# 4U-4452.net
KiCad netlist of a schematic drawn in EAGLE
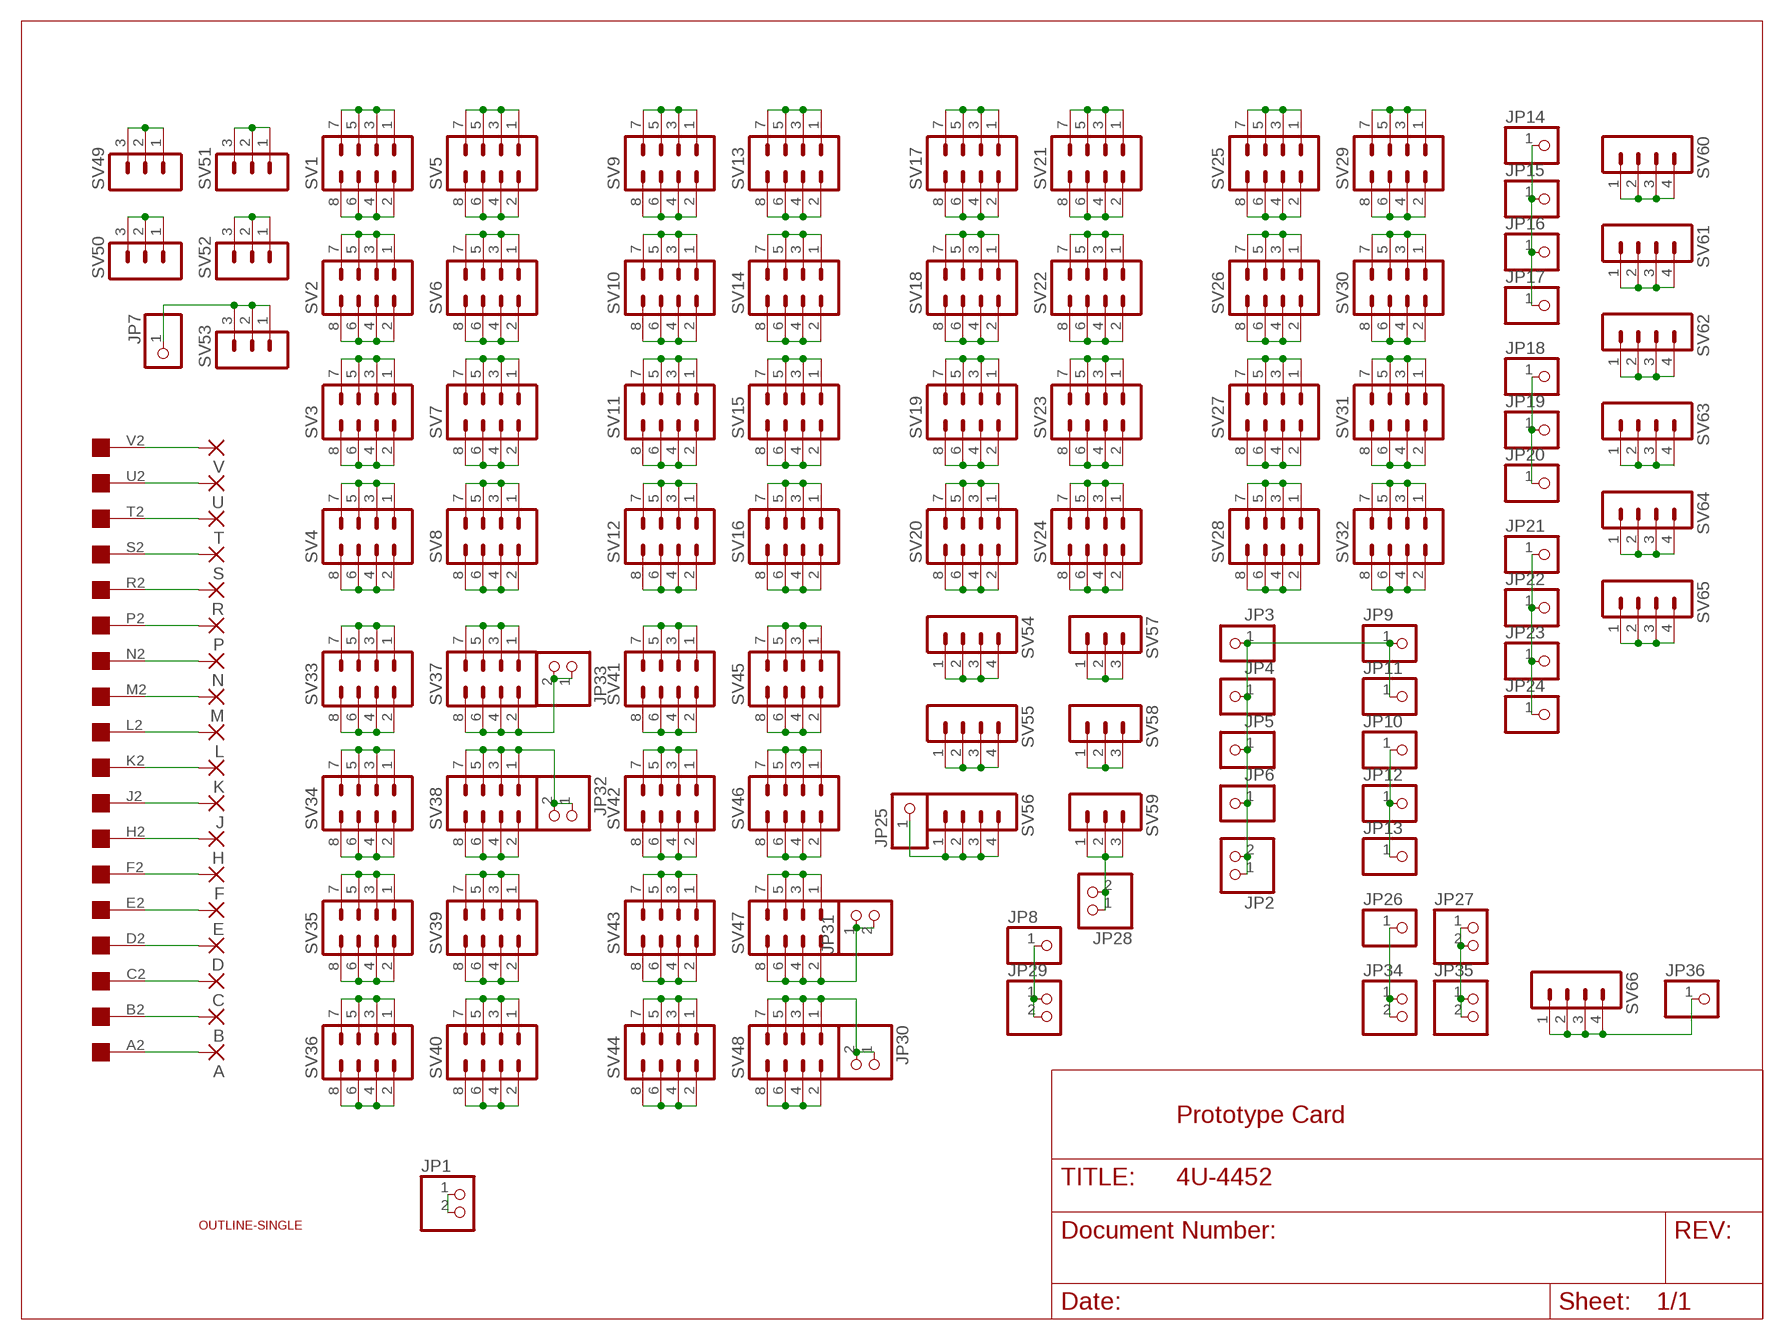
[diagram p0: schematic, sheet 1]

(export (version "E")
  (design (tool "Eeschema 10.0.6"))
  (components
    (comp (ref "A")
      (value "3,17/1,1")
      (footprint "eagle-import:3,17_1,1")
      (libsource (lib "eagle-import") (part "3,17/1,1"))
    )
    (comp (ref "B")
      (value "3,17/1,1")
      (footprint "eagle-import:3,17_1,1")
      (libsource (lib "eagle-import") (part "3,17/1,1"))
    )
    (comp (ref "C")
      (value "3,17/1,1")
      (footprint "eagle-import:3,17_1,1")
      (libsource (lib "eagle-import") (part "3,17/1,1"))
    )
    (comp (ref "D")
      (value "3,17/1,1")
      (footprint "eagle-import:3,17_1,1")
      (libsource (lib "eagle-import") (part "3,17/1,1"))
    )
    (comp (ref "E")
      (value "3,17/1,1")
      (footprint "eagle-import:3,17_1,1")
      (libsource (lib "eagle-import") (part "3,17/1,1"))
    )
    (comp (ref "F")
      (value "3,17/1,1")
      (footprint "eagle-import:3,17_1,1")
      (libsource (lib "eagle-import") (part "3,17/1,1"))
    )
    (comp (ref "H")
      (value "3,17/1,1")
      (footprint "eagle-import:3,17_1,1")
      (libsource (lib "eagle-import") (part "3,17/1,1"))
    )
    (comp (ref "J")
      (value "3,17/1,1")
      (footprint "eagle-import:3,17_1,1")
      (libsource (lib "eagle-import") (part "3,17/1,1"))
    )
    (comp (ref "JP1")
      (value "PINHD-1X2")
      (footprint "eagle-import:1X02")
      (libsource (lib "eagle-import") (part "PINHD-1X2"))
    )
    (comp (ref "JP2")
      (value "PINHD-1X2")
      (footprint "eagle-import:1X02")
      (libsource (lib "eagle-import") (part "PINHD-1X2"))
    )
    (comp (ref "JP3")
      (value "PINHD-1X1")
      (footprint "eagle-import:1X01")
      (libsource (lib "eagle-import") (part "PINHD-1X1"))
    )
    (comp (ref "JP4")
      (value "PINHD-1X1")
      (footprint "eagle-import:1X01")
      (libsource (lib "eagle-import") (part "PINHD-1X1"))
    )
    (comp (ref "JP5")
      (value "PINHD-1X1")
      (footprint "eagle-import:1X01")
      (libsource (lib "eagle-import") (part "PINHD-1X1"))
    )
    (comp (ref "JP6")
      (value "PINHD-1X1")
      (footprint "eagle-import:1X01")
      (libsource (lib "eagle-import") (part "PINHD-1X1"))
    )
    (comp (ref "JP7")
      (value "PINHD-1X1")
      (footprint "eagle-import:1X01")
      (libsource (lib "eagle-import") (part "PINHD-1X1"))
    )
    (comp (ref "JP8")
      (value "PINHD-1X1")
      (footprint "eagle-import:1X01")
      (libsource (lib "eagle-import") (part "PINHD-1X1"))
    )
    (comp (ref "JP9")
      (value "PINHD-1X1")
      (footprint "eagle-import:1X01")
      (libsource (lib "eagle-import") (part "PINHD-1X1"))
    )
    (comp (ref "JP10")
      (value "PINHD-1X1")
      (footprint "eagle-import:1X01")
      (libsource (lib "eagle-import") (part "PINHD-1X1"))
    )
    (comp (ref "JP11")
      (value "PINHD-1X1")
      (footprint "eagle-import:1X01")
      (libsource (lib "eagle-import") (part "PINHD-1X1"))
    )
    (comp (ref "JP12")
      (value "PINHD-1X1")
      (footprint "eagle-import:1X01")
      (libsource (lib "eagle-import") (part "PINHD-1X1"))
    )
    (comp (ref "JP13")
      (value "PINHD-1X1")
      (footprint "eagle-import:1X01")
      (libsource (lib "eagle-import") (part "PINHD-1X1"))
    )
    (comp (ref "JP14")
      (value "PINHD-1X1")
      (footprint "eagle-import:1X01")
      (libsource (lib "eagle-import") (part "PINHD-1X1"))
    )
    (comp (ref "JP15")
      (value "PINHD-1X1")
      (footprint "eagle-import:1X01")
      (libsource (lib "eagle-import") (part "PINHD-1X1"))
    )
    (comp (ref "JP16")
      (value "PINHD-1X1")
      (footprint "eagle-import:1X01")
      (libsource (lib "eagle-import") (part "PINHD-1X1"))
    )
    (comp (ref "JP17")
      (value "PINHD-1X1")
      (footprint "eagle-import:1X01")
      (libsource (lib "eagle-import") (part "PINHD-1X1"))
    )
    (comp (ref "JP18")
      (value "PINHD-1X1")
      (footprint "eagle-import:1X01")
      (libsource (lib "eagle-import") (part "PINHD-1X1"))
    )
    (comp (ref "JP19")
      (value "PINHD-1X1")
      (footprint "eagle-import:1X01")
      (libsource (lib "eagle-import") (part "PINHD-1X1"))
    )
    (comp (ref "JP20")
      (value "PINHD-1X1")
      (footprint "eagle-import:1X01")
      (libsource (lib "eagle-import") (part "PINHD-1X1"))
    )
    (comp (ref "JP21")
      (value "PINHD-1X1")
      (footprint "eagle-import:1X01")
      (libsource (lib "eagle-import") (part "PINHD-1X1"))
    )
    (comp (ref "JP22")
      (value "PINHD-1X1")
      (footprint "eagle-import:1X01")
      (libsource (lib "eagle-import") (part "PINHD-1X1"))
    )
    (comp (ref "JP23")
      (value "PINHD-1X1")
      (footprint "eagle-import:1X01")
      (libsource (lib "eagle-import") (part "PINHD-1X1"))
    )
    (comp (ref "JP24")
      (value "PINHD-1X1")
      (footprint "eagle-import:1X01")
      (libsource (lib "eagle-import") (part "PINHD-1X1"))
    )
    (comp (ref "JP25")
      (value "PINHD-1X1")
      (footprint "eagle-import:1X01")
      (libsource (lib "eagle-import") (part "PINHD-1X1"))
    )
    (comp (ref "JP26")
      (value "PINHD-1X1")
      (footprint "eagle-import:1X01")
      (libsource (lib "eagle-import") (part "PINHD-1X1"))
    )
    (comp (ref "JP27")
      (value "PINHD-1X2")
      (footprint "eagle-import:1X02")
      (libsource (lib "eagle-import") (part "PINHD-1X2"))
    )
    (comp (ref "JP28")
      (value "PINHD-1X2")
      (footprint "eagle-import:1X02")
      (libsource (lib "eagle-import") (part "PINHD-1X2"))
    )
    (comp (ref "JP29")
      (value "PINHD-1X2")
      (footprint "eagle-import:1X02")
      (libsource (lib "eagle-import") (part "PINHD-1X2"))
    )
    (comp (ref "JP30")
      (value "PINHD-1X2")
      (footprint "eagle-import:1X02")
      (libsource (lib "eagle-import") (part "PINHD-1X2"))
    )
    (comp (ref "JP31")
      (value "PINHD-1X2")
      (footprint "eagle-import:1X02")
      (libsource (lib "eagle-import") (part "PINHD-1X2"))
    )
    (comp (ref "JP32")
      (value "PINHD-1X2")
      (footprint "eagle-import:1X02")
      (libsource (lib "eagle-import") (part "PINHD-1X2"))
    )
    (comp (ref "JP33")
      (value "PINHD-1X2")
      (footprint "eagle-import:1X02")
      (libsource (lib "eagle-import") (part "PINHD-1X2"))
    )
    (comp (ref "JP34")
      (value "PINHD-1X2")
      (footprint "eagle-import:1X02")
      (libsource (lib "eagle-import") (part "PINHD-1X2"))
    )
    (comp (ref "JP35")
      (value "PINHD-1X2")
      (footprint "eagle-import:1X02")
      (libsource (lib "eagle-import") (part "PINHD-1X2"))
    )
    (comp (ref "JP36")
      (value "PINHD-1X1")
      (footprint "eagle-import:1X01")
      (libsource (lib "eagle-import") (part "PINHD-1X1"))
    )
    (comp (ref "K")
      (value "3,17/1,1")
      (footprint "eagle-import:3,17_1,1")
      (libsource (lib "eagle-import") (part "3,17/1,1"))
    )
    (comp (ref "L")
      (value "3,17/1,1")
      (footprint "eagle-import:3,17_1,1")
      (libsource (lib "eagle-import") (part "3,17/1,1"))
    )
    (comp (ref "M")
      (value "3,17/1,1")
      (footprint "eagle-import:3,17_1,1")
      (libsource (lib "eagle-import") (part "3,17/1,1"))
    )
    (comp (ref "N")
      (value "3,17/1,1")
      (footprint "eagle-import:3,17_1,1")
      (libsource (lib "eagle-import") (part "3,17/1,1"))
    )
    (comp (ref "P")
      (value "3,17/1,1")
      (footprint "eagle-import:3,17_1,1")
      (libsource (lib "eagle-import") (part "3,17/1,1"))
    )
    (comp (ref "R")
      (value "3,17/1,1")
      (footprint "eagle-import:3,17_1,1")
      (libsource (lib "eagle-import") (part "3,17/1,1"))
    )
    (comp (ref "S")
      (value "3,17/1,1")
      (footprint "eagle-import:3,17_1,1")
      (libsource (lib "eagle-import") (part "3,17/1,1"))
    )
    (comp (ref "SV1")
      (value "MA04-2")
      (footprint "eagle-import:MA04-2")
      (libsource (lib "eagle-import") (part "MA04-2"))
    )
    (comp (ref "SV2")
      (value "MA04-2")
      (footprint "eagle-import:MA04-2")
      (libsource (lib "eagle-import") (part "MA04-2"))
    )
    (comp (ref "SV3")
      (value "MA04-2")
      (footprint "eagle-import:MA04-2")
      (libsource (lib "eagle-import") (part "MA04-2"))
    )
    (comp (ref "SV4")
      (value "MA04-2")
      (footprint "eagle-import:MA04-2")
      (libsource (lib "eagle-import") (part "MA04-2"))
    )
    (comp (ref "SV5")
      (value "MA04-2")
      (footprint "eagle-import:MA04-2")
      (libsource (lib "eagle-import") (part "MA04-2"))
    )
    (comp (ref "SV6")
      (value "MA04-2")
      (footprint "eagle-import:MA04-2")
      (libsource (lib "eagle-import") (part "MA04-2"))
    )
    (comp (ref "SV7")
      (value "MA04-2")
      (footprint "eagle-import:MA04-2")
      (libsource (lib "eagle-import") (part "MA04-2"))
    )
    (comp (ref "SV8")
      (value "MA04-2")
      (footprint "eagle-import:MA04-2")
      (libsource (lib "eagle-import") (part "MA04-2"))
    )
    (comp (ref "SV9")
      (value "MA04-2")
      (footprint "eagle-import:MA04-2")
      (libsource (lib "eagle-import") (part "MA04-2"))
    )
    (comp (ref "SV10")
      (value "MA04-2")
      (footprint "eagle-import:MA04-2")
      (libsource (lib "eagle-import") (part "MA04-2"))
    )
    (comp (ref "SV11")
      (value "MA04-2")
      (footprint "eagle-import:MA04-2")
      (libsource (lib "eagle-import") (part "MA04-2"))
    )
    (comp (ref "SV12")
      (value "MA04-2")
      (footprint "eagle-import:MA04-2")
      (libsource (lib "eagle-import") (part "MA04-2"))
    )
    (comp (ref "SV13")
      (value "MA04-2")
      (footprint "eagle-import:MA04-2")
      (libsource (lib "eagle-import") (part "MA04-2"))
    )
    (comp (ref "SV14")
      (value "MA04-2")
      (footprint "eagle-import:MA04-2")
      (libsource (lib "eagle-import") (part "MA04-2"))
    )
    (comp (ref "SV15")
      (value "MA04-2")
      (footprint "eagle-import:MA04-2")
      (libsource (lib "eagle-import") (part "MA04-2"))
    )
    (comp (ref "SV16")
      (value "MA04-2")
      (footprint "eagle-import:MA04-2")
      (libsource (lib "eagle-import") (part "MA04-2"))
    )
    (comp (ref "SV17")
      (value "MA04-2")
      (footprint "eagle-import:MA04-2")
      (libsource (lib "eagle-import") (part "MA04-2"))
    )
    (comp (ref "SV18")
      (value "MA04-2")
      (footprint "eagle-import:MA04-2")
      (libsource (lib "eagle-import") (part "MA04-2"))
    )
    (comp (ref "SV19")
      (value "MA04-2")
      (footprint "eagle-import:MA04-2")
      (libsource (lib "eagle-import") (part "MA04-2"))
    )
    (comp (ref "SV20")
      (value "MA04-2")
      (footprint "eagle-import:MA04-2")
      (libsource (lib "eagle-import") (part "MA04-2"))
    )
    (comp (ref "SV21")
      (value "MA04-2")
      (footprint "eagle-import:MA04-2")
      (libsource (lib "eagle-import") (part "MA04-2"))
    )
    (comp (ref "SV22")
      (value "MA04-2")
      (footprint "eagle-import:MA04-2")
      (libsource (lib "eagle-import") (part "MA04-2"))
    )
    (comp (ref "SV23")
      (value "MA04-2")
      (footprint "eagle-import:MA04-2")
      (libsource (lib "eagle-import") (part "MA04-2"))
    )
    (comp (ref "SV24")
      (value "MA04-2")
      (footprint "eagle-import:MA04-2")
      (libsource (lib "eagle-import") (part "MA04-2"))
    )
    (comp (ref "SV25")
      (value "MA04-2")
      (footprint "eagle-import:MA04-2")
      (libsource (lib "eagle-import") (part "MA04-2"))
    )
    (comp (ref "SV26")
      (value "MA04-2")
      (footprint "eagle-import:MA04-2")
      (libsource (lib "eagle-import") (part "MA04-2"))
    )
    (comp (ref "SV27")
      (value "MA04-2")
      (footprint "eagle-import:MA04-2")
      (libsource (lib "eagle-import") (part "MA04-2"))
    )
    (comp (ref "SV28")
      (value "MA04-2")
      (footprint "eagle-import:MA04-2")
      (libsource (lib "eagle-import") (part "MA04-2"))
    )
    (comp (ref "SV29")
      (value "MA04-2")
      (footprint "eagle-import:MA04-2")
      (libsource (lib "eagle-import") (part "MA04-2"))
    )
    (comp (ref "SV30")
      (value "MA04-2")
      (footprint "eagle-import:MA04-2")
      (libsource (lib "eagle-import") (part "MA04-2"))
    )
    (comp (ref "SV31")
      (value "MA04-2")
      (footprint "eagle-import:MA04-2")
      (libsource (lib "eagle-import") (part "MA04-2"))
    )
    (comp (ref "SV32")
      (value "MA04-2")
      (footprint "eagle-import:MA04-2")
      (libsource (lib "eagle-import") (part "MA04-2"))
    )
    (comp (ref "SV33")
      (value "MA04-2")
      (footprint "eagle-import:MA04-2")
      (libsource (lib "eagle-import") (part "MA04-2"))
    )
    (comp (ref "SV34")
      (value "MA04-2")
      (footprint "eagle-import:MA04-2")
      (libsource (lib "eagle-import") (part "MA04-2"))
    )
    (comp (ref "SV35")
      (value "MA04-2")
      (footprint "eagle-import:MA04-2")
      (libsource (lib "eagle-import") (part "MA04-2"))
    )
    (comp (ref "SV36")
      (value "MA04-2")
      (footprint "eagle-import:MA04-2")
      (libsource (lib "eagle-import") (part "MA04-2"))
    )
    (comp (ref "SV37")
      (value "MA04-2")
      (footprint "eagle-import:MA04-2")
      (libsource (lib "eagle-import") (part "MA04-2"))
    )
    (comp (ref "SV38")
      (value "MA04-2")
      (footprint "eagle-import:MA04-2")
      (libsource (lib "eagle-import") (part "MA04-2"))
    )
    (comp (ref "SV39")
      (value "MA04-2")
      (footprint "eagle-import:MA04-2")
      (libsource (lib "eagle-import") (part "MA04-2"))
    )
    (comp (ref "SV40")
      (value "MA04-2")
      (footprint "eagle-import:MA04-2")
      (libsource (lib "eagle-import") (part "MA04-2"))
    )
    (comp (ref "SV41")
      (value "MA04-2")
      (footprint "eagle-import:MA04-2")
      (libsource (lib "eagle-import") (part "MA04-2"))
    )
    (comp (ref "SV42")
      (value "MA04-2")
      (footprint "eagle-import:MA04-2")
      (libsource (lib "eagle-import") (part "MA04-2"))
    )
    (comp (ref "SV43")
      (value "MA04-2")
      (footprint "eagle-import:MA04-2")
      (libsource (lib "eagle-import") (part "MA04-2"))
    )
    (comp (ref "SV44")
      (value "MA04-2")
      (footprint "eagle-import:MA04-2")
      (libsource (lib "eagle-import") (part "MA04-2"))
    )
    (comp (ref "SV45")
      (value "MA04-2")
      (footprint "eagle-import:MA04-2")
      (libsource (lib "eagle-import") (part "MA04-2"))
    )
    (comp (ref "SV46")
      (value "MA04-2")
      (footprint "eagle-import:MA04-2")
      (libsource (lib "eagle-import") (part "MA04-2"))
    )
    (comp (ref "SV47")
      (value "MA04-2")
      (footprint "eagle-import:MA04-2")
      (libsource (lib "eagle-import") (part "MA04-2"))
    )
    (comp (ref "SV48")
      (value "MA04-2")
      (footprint "eagle-import:MA04-2")
      (libsource (lib "eagle-import") (part "MA04-2"))
    )
    (comp (ref "SV49")
      (value "MA03-1")
      (footprint "eagle-import:MA03-1")
      (libsource (lib "eagle-import") (part "MA03-1"))
    )
    (comp (ref "SV50")
      (value "MA03-1")
      (footprint "eagle-import:MA03-1")
      (libsource (lib "eagle-import") (part "MA03-1"))
    )
    (comp (ref "SV51")
      (value "MA03-1")
      (footprint "eagle-import:MA03-1")
      (libsource (lib "eagle-import") (part "MA03-1"))
    )
    (comp (ref "SV52")
      (value "MA03-1")
      (footprint "eagle-import:MA03-1")
      (libsource (lib "eagle-import") (part "MA03-1"))
    )
    (comp (ref "SV53")
      (value "MA03-1")
      (footprint "eagle-import:MA03-1")
      (libsource (lib "eagle-import") (part "MA03-1"))
    )
    (comp (ref "SV54")
      (value "MA04-1")
      (footprint "eagle-import:MA04-1")
      (libsource (lib "eagle-import") (part "MA04-1"))
    )
    (comp (ref "SV55")
      (value "MA04-1")
      (footprint "eagle-import:MA04-1")
      (libsource (lib "eagle-import") (part "MA04-1"))
    )
    (comp (ref "SV56")
      (value "MA04-1")
      (footprint "eagle-import:MA04-1")
      (libsource (lib "eagle-import") (part "MA04-1"))
    )
    (comp (ref "SV57")
      (value "MA03-1")
      (footprint "eagle-import:MA03-1")
      (libsource (lib "eagle-import") (part "MA03-1"))
    )
    (comp (ref "SV58")
      (value "MA03-1")
      (footprint "eagle-import:MA03-1")
      (libsource (lib "eagle-import") (part "MA03-1"))
    )
    (comp (ref "SV59")
      (value "MA03-1")
      (footprint "eagle-import:MA03-1")
      (libsource (lib "eagle-import") (part "MA03-1"))
    )
    (comp (ref "SV60")
      (value "MA04-1")
      (footprint "eagle-import:MA04-1")
      (libsource (lib "eagle-import") (part "MA04-1"))
    )
    (comp (ref "SV61")
      (value "MA04-1")
      (footprint "eagle-import:MA04-1")
      (libsource (lib "eagle-import") (part "MA04-1"))
    )
    (comp (ref "SV62")
      (value "MA04-1")
      (footprint "eagle-import:MA04-1")
      (libsource (lib "eagle-import") (part "MA04-1"))
    )
    (comp (ref "SV63")
      (value "MA04-1")
      (footprint "eagle-import:MA04-1")
      (libsource (lib "eagle-import") (part "MA04-1"))
    )
    (comp (ref "SV64")
      (value "MA04-1")
      (footprint "eagle-import:MA04-1")
      (libsource (lib "eagle-import") (part "MA04-1"))
    )
    (comp (ref "SV65")
      (value "MA04-1")
      (footprint "eagle-import:MA04-1")
      (libsource (lib "eagle-import") (part "MA04-1"))
    )
    (comp (ref "SV66")
      (value "MA04-1")
      (footprint "eagle-import:MA04-1")
      (libsource (lib "eagle-import") (part "MA04-1"))
    )
    (comp (ref "T")
      (value "3,17/1,1")
      (footprint "eagle-import:3,17_1,1")
      (libsource (lib "eagle-import") (part "3,17/1,1"))
    )
    (comp (ref "U")
      (value "3,17/1,1")
      (footprint "eagle-import:3,17_1,1")
      (libsource (lib "eagle-import") (part "3,17/1,1"))
    )
    (comp (ref "U$1")
      (value "EDGE-1")
      (footprint "eagle-import:EDGE-CON1")
      (libsource (lib "eagle-import") (part "EDGE-1"))
    )
    (comp (ref "U$2")
      (value "OUTLINE-SINGLE")
      (footprint "eagle-import:SINGLE")
      (libsource (lib "eagle-import") (part "OUTLINE-SINGLE"))
    )
    (comp (ref "V")
      (value "3,17/1,1")
      (footprint "eagle-import:3,17_1,1")
      (libsource (lib "eagle-import") (part "3,17/1,1"))
    )
  )
  (nets
    (net (code "1") (name "Net-(A-P)") (class "Default")
      (node (ref "A") (pin "1") (pinfunction "P_1") (pintype "passive"))
      (node (ref "U$1") (pin "A2") (pinfunction "1_A2") (pintype "bidirectional"))
    )
    (net (code "2") (name "Net-(B-P)") (class "Default")
      (node (ref "B") (pin "1") (pinfunction "P_1") (pintype "passive"))
      (node (ref "U$1") (pin "B2") (pinfunction "1_B2") (pintype "bidirectional"))
    )
    (net (code "3") (name "Net-(C-P)") (class "Default")
      (node (ref "C") (pin "1") (pinfunction "P_1") (pintype "passive"))
      (node (ref "U$1") (pin "C2") (pinfunction "1_C2") (pintype "bidirectional"))
    )
    (net (code "4") (name "Net-(D-P)") (class "Default")
      (node (ref "D") (pin "1") (pinfunction "P_1") (pintype "passive"))
      (node (ref "U$1") (pin "D2") (pinfunction "1_D2") (pintype "bidirectional"))
    )
    (net (code "5") (name "Net-(E-P)") (class "Default")
      (node (ref "E") (pin "1") (pinfunction "P_1") (pintype "passive"))
      (node (ref "U$1") (pin "E2") (pinfunction "1_E2") (pintype "bidirectional"))
    )
    (net (code "6") (name "Net-(F-P)") (class "Default")
      (node (ref "F") (pin "1") (pinfunction "P_1") (pintype "passive"))
      (node (ref "U$1") (pin "F2") (pinfunction "1_F2") (pintype "bidirectional"))
    )
    (net (code "7") (name "Net-(H-P)") (class "Default")
      (node (ref "H") (pin "1") (pinfunction "P_1") (pintype "passive"))
      (node (ref "U$1") (pin "H2") (pinfunction "1_H2") (pintype "bidirectional"))
    )
    (net (code "8") (name "Net-(J-P)") (class "Default")
      (node (ref "J") (pin "1") (pinfunction "P_1") (pintype "passive"))
      (node (ref "U$1") (pin "J2") (pinfunction "1_J2") (pintype "bidirectional"))
    )
    (net (code "9") (name "Net-(JP1-Pad1)") (class "Default")
      (node (ref "JP1") (pin "1") (pinfunction "1_1") (pintype "passive"))
      (node (ref "JP1") (pin "2") (pinfunction "2_2") (pintype "passive"))
    )
    (net (code "10") (name "Net-(JP7-Pad1)") (class "Default")
      (node (ref "JP7") (pin "1") (pinfunction "1_1") (pintype "passive"))
      (node (ref "SV53") (pin "1") (pinfunction "1_1") (pintype "passive"))
      (node (ref "SV53") (pin "2") (pinfunction "2_2") (pintype "passive"))
      (node (ref "SV53") (pin "3") (pinfunction "3_3") (pintype "passive"))
    )
    (net (code "11") (name "Net-(JP10-Pad1)") (class "Default")
      (node (ref "JP10") (pin "1") (pinfunction "1_1") (pintype "passive"))
      (node (ref "JP12") (pin "1") (pinfunction "1_1") (pintype "passive"))
      (node (ref "JP13") (pin "1") (pinfunction "1_1") (pintype "passive"))
    )
    (net (code "12") (name "Net-(JP11-Pad1)") (class "Default")
      (node (ref "JP11") (pin "1") (pinfunction "1_1") (pintype "passive"))
      (node (ref "JP2") (pin "1") (pinfunction "1_1") (pintype "passive"))
      (node (ref "JP2") (pin "2") (pinfunction "2_2") (pintype "passive"))
      (node (ref "JP3") (pin "1") (pinfunction "1_1") (pintype "passive"))
      (node (ref "JP4") (pin "1") (pinfunction "1_1") (pintype "passive"))
      (node (ref "JP5") (pin "1") (pinfunction "1_1") (pintype "passive"))
      (node (ref "JP6") (pin "1") (pinfunction "1_1") (pintype "passive"))
      (node (ref "JP9") (pin "1") (pinfunction "1_1") (pintype "passive"))
    )
    (net (code "13") (name "Net-(JP14-Pad1)") (class "Default")
      (node (ref "JP14") (pin "1") (pinfunction "1_1") (pintype "passive"))
      (node (ref "JP15") (pin "1") (pinfunction "1_1") (pintype "passive"))
      (node (ref "JP16") (pin "1") (pinfunction "1_1") (pintype "passive"))
      (node (ref "JP17") (pin "1") (pinfunction "1_1") (pintype "passive"))
    )
    (net (code "14") (name "Net-(JP18-Pad1)") (class "Default")
      (node (ref "JP18") (pin "1") (pinfunction "1_1") (pintype "passive"))
      (node (ref "JP19") (pin "1") (pinfunction "1_1") (pintype "passive"))
      (node (ref "JP20") (pin "1") (pinfunction "1_1") (pintype "passive"))
    )
    (net (code "15") (name "Net-(JP21-Pad1)") (class "Default")
      (node (ref "JP21") (pin "1") (pinfunction "1_1") (pintype "passive"))
      (node (ref "JP22") (pin "1") (pinfunction "1_1") (pintype "passive"))
      (node (ref "JP23") (pin "1") (pinfunction "1_1") (pintype "passive"))
      (node (ref "JP24") (pin "1") (pinfunction "1_1") (pintype "passive"))
    )
    (net (code "16") (name "Net-(JP25-Pad1)") (class "Default")
      (node (ref "JP25") (pin "1") (pinfunction "1_1") (pintype "passive"))
      (node (ref "SV56") (pin "1") (pinfunction "1_1") (pintype "passive"))
      (node (ref "SV56") (pin "2") (pinfunction "2_2") (pintype "passive"))
      (node (ref "SV56") (pin "3") (pinfunction "3_3") (pintype "passive"))
      (node (ref "SV56") (pin "4") (pinfunction "4_4") (pintype "passive"))
    )
    (net (code "17") (name "Net-(JP26-Pad1)") (class "Default")
      (node (ref "JP26") (pin "1") (pinfunction "1_1") (pintype "passive"))
      (node (ref "JP34") (pin "1") (pinfunction "1_1") (pintype "passive"))
      (node (ref "JP34") (pin "2") (pinfunction "2_2") (pintype "passive"))
    )
    (net (code "18") (name "Net-(JP27-Pad1)") (class "Default")
      (node (ref "JP27") (pin "1") (pinfunction "1_1") (pintype "passive"))
      (node (ref "JP27") (pin "2") (pinfunction "2_2") (pintype "passive"))
      (node (ref "JP35") (pin "1") (pinfunction "1_1") (pintype "passive"))
      (node (ref "JP35") (pin "2") (pinfunction "2_2") (pintype "passive"))
    )
    (net (code "19") (name "Net-(JP28-Pad1)") (class "Default")
      (node (ref "JP28") (pin "1") (pinfunction "1_1") (pintype "passive"))
      (node (ref "JP28") (pin "2") (pinfunction "2_2") (pintype "passive"))
      (node (ref "SV59") (pin "1") (pinfunction "1_1") (pintype "passive"))
      (node (ref "SV59") (pin "2") (pinfunction "2_2") (pintype "passive"))
      (node (ref "SV59") (pin "3") (pinfunction "3_3") (pintype "passive"))
    )
    (net (code "20") (name "Net-(JP29-Pad1)") (class "Default")
      (node (ref "JP29") (pin "1") (pinfunction "1_1") (pintype "passive"))
      (node (ref "JP29") (pin "2") (pinfunction "2_2") (pintype "passive"))
      (node (ref "JP8") (pin "1") (pinfunction "1_1") (pintype "passive"))
    )
    (net (code "21") (name "Net-(JP30-Pad1)") (class "Default")
      (node (ref "JP30") (pin "1") (pinfunction "1_1") (pintype "passive"))
      (node (ref "JP30") (pin "2") (pinfunction "2_2") (pintype "passive"))
      (node (ref "SV48") (pin "1") (pinfunction "1_1") (pintype "passive"))
      (node (ref "SV48") (pin "3") (pinfunction "3_3") (pintype "passive"))
      (node (ref "SV48") (pin "5") (pinfunction "5_5") (pintype "passive"))
      (node (ref "SV48") (pin "7") (pinfunction "7_7") (pintype "passive"))
    )
    (net (code "22") (name "Net-(JP31-Pad1)") (class "Default")
      (node (ref "JP31") (pin "1") (pinfunction "1_1") (pintype "passive"))
      (node (ref "JP31") (pin "2") (pinfunction "2_2") (pintype "passive"))
      (node (ref "SV47") (pin "2") (pinfunction "2_2") (pintype "passive"))
      (node (ref "SV47") (pin "4") (pinfunction "4_4") (pintype "passive"))
      (node (ref "SV47") (pin "6") (pinfunction "6_6") (pintype "passive"))
      (node (ref "SV47") (pin "8") (pinfunction "8_8") (pintype "passive"))
    )
    (net (code "23") (name "Net-(JP32-Pad1)") (class "Default")
      (node (ref "JP32") (pin "1") (pinfunction "1_1") (pintype "passive"))
      (node (ref "JP32") (pin "2") (pinfunction "2_2") (pintype "passive"))
      (node (ref "SV38") (pin "1") (pinfunction "1_1") (pintype "passive"))
      (node (ref "SV38") (pin "3") (pinfunction "3_3") (pintype "passive"))
      (node (ref "SV38") (pin "5") (pinfunction "5_5") (pintype "passive"))
      (node (ref "SV38") (pin "7") (pinfunction "7_7") (pintype "passive"))
    )
    (net (code "24") (name "Net-(JP33-Pad1)") (class "Default")
      (node (ref "JP33") (pin "1") (pinfunction "1_1") (pintype "passive"))
      (node (ref "JP33") (pin "2") (pinfunction "2_2") (pintype "passive"))
      (node (ref "SV37") (pin "2") (pinfunction "2_2") (pintype "passive"))
      (node (ref "SV37") (pin "4") (pinfunction "4_4") (pintype "passive"))
      (node (ref "SV37") (pin "6") (pinfunction "6_6") (pintype "passive"))
      (node (ref "SV37") (pin "8") (pinfunction "8_8") (pintype "passive"))
    )
    (net (code "25") (name "Net-(JP36-Pad1)") (class "Default")
      (node (ref "JP36") (pin "1") (pinfunction "1_1") (pintype "passive"))
      (node (ref "SV66") (pin "1") (pinfunction "1_1") (pintype "passive"))
      (node (ref "SV66") (pin "2") (pinfunction "2_2") (pintype "passive"))
      (node (ref "SV66") (pin "3") (pinfunction "3_3") (pintype "passive"))
      (node (ref "SV66") (pin "4") (pinfunction "4_4") (pintype "passive"))
    )
    (net (code "26") (name "Net-(K-P)") (class "Default")
      (node (ref "K") (pin "1") (pinfunction "P_1") (pintype "passive"))
      (node (ref "U$1") (pin "K2") (pinfunction "1_K2") (pintype "bidirectional"))
    )
    (net (code "27") (name "Net-(L-P)") (class "Default")
      (node (ref "L") (pin "1") (pinfunction "P_1") (pintype "passive"))
      (node (ref "U$1") (pin "L2") (pinfunction "1_L2") (pintype "bidirectional"))
    )
    (net (code "28") (name "Net-(M-P)") (class "Default")
      (node (ref "M") (pin "1") (pinfunction "P_1") (pintype "passive"))
      (node (ref "U$1") (pin "M2") (pinfunction "1_M2") (pintype "bidirectional"))
    )
    (net (code "29") (name "Net-(N-P)") (class "Default")
      (node (ref "N") (pin "1") (pinfunction "P_1") (pintype "passive"))
      (node (ref "U$1") (pin "N2") (pinfunction "1_N2") (pintype "bidirectional"))
    )
    (net (code "30") (name "Net-(P-P)") (class "Default")
      (node (ref "P") (pin "1") (pinfunction "P_1") (pintype "passive"))
      (node (ref "U$1") (pin "P2") (pinfunction "1_P2") (pintype "bidirectional"))
    )
    (net (code "31") (name "Net-(R-P)") (class "Default")
      (node (ref "R") (pin "1") (pinfunction "P_1") (pintype "passive"))
      (node (ref "U$1") (pin "R2") (pinfunction "1_R2") (pintype "bidirectional"))
    )
    (net (code "32") (name "Net-(S-P)") (class "Default")
      (node (ref "S") (pin "1") (pinfunction "P_1") (pintype "passive"))
      (node (ref "U$1") (pin "S2") (pinfunction "1_S2") (pintype "bidirectional"))
    )
    (net (code "33") (name "Net-(SV1-Pad1)") (class "Default")
      (node (ref "SV1") (pin "1") (pinfunction "1_1") (pintype "passive"))
      (node (ref "SV1") (pin "3") (pinfunction "3_3") (pintype "passive"))
      (node (ref "SV1") (pin "5") (pinfunction "5_5") (pintype "passive"))
      (node (ref "SV1") (pin "7") (pinfunction "7_7") (pintype "passive"))
    )
    (net (code "34") (name "Net-(SV1-Pad2)") (class "Default")
      (node (ref "SV1") (pin "2") (pinfunction "2_2") (pintype "passive"))
      (node (ref "SV1") (pin "4") (pinfunction "4_4") (pintype "passive"))
      (node (ref "SV1") (pin "6") (pinfunction "6_6") (pintype "passive"))
      (node (ref "SV1") (pin "8") (pinfunction "8_8") (pintype "passive"))
    )
    (net (code "35") (name "Net-(SV2-Pad1)") (class "Default")
      (node (ref "SV2") (pin "1") (pinfunction "1_1") (pintype "passive"))
      (node (ref "SV2") (pin "3") (pinfunction "3_3") (pintype "passive"))
      (node (ref "SV2") (pin "5") (pinfunction "5_5") (pintype "passive"))
      (node (ref "SV2") (pin "7") (pinfunction "7_7") (pintype "passive"))
    )
    (net (code "36") (name "Net-(SV2-Pad2)") (class "Default")
      (node (ref "SV2") (pin "2") (pinfunction "2_2") (pintype "passive"))
      (node (ref "SV2") (pin "4") (pinfunction "4_4") (pintype "passive"))
      (node (ref "SV2") (pin "6") (pinfunction "6_6") (pintype "passive"))
      (node (ref "SV2") (pin "8") (pinfunction "8_8") (pintype "passive"))
    )
    (net (code "37") (name "Net-(SV3-Pad1)") (class "Default")
      (node (ref "SV3") (pin "1") (pinfunction "1_1") (pintype "passive"))
      (node (ref "SV3") (pin "3") (pinfunction "3_3") (pintype "passive"))
      (node (ref "SV3") (pin "5") (pinfunction "5_5") (pintype "passive"))
      (node (ref "SV3") (pin "7") (pinfunction "7_7") (pintype "passive"))
    )
    (net (code "38") (name "Net-(SV3-Pad2)") (class "Default")
      (node (ref "SV3") (pin "2") (pinfunction "2_2") (pintype "passive"))
      (node (ref "SV3") (pin "4") (pinfunction "4_4") (pintype "passive"))
      (node (ref "SV3") (pin "6") (pinfunction "6_6") (pintype "passive"))
      (node (ref "SV3") (pin "8") (pinfunction "8_8") (pintype "passive"))
    )
    (net (code "39") (name "Net-(SV4-Pad1)") (class "Default")
      (node (ref "SV4") (pin "1") (pinfunction "1_1") (pintype "passive"))
      (node (ref "SV4") (pin "3") (pinfunction "3_3") (pintype "passive"))
      (node (ref "SV4") (pin "5") (pinfunction "5_5") (pintype "passive"))
      (node (ref "SV4") (pin "7") (pinfunction "7_7") (pintype "passive"))
    )
    (net (code "40") (name "Net-(SV4-Pad2)") (class "Default")
      (node (ref "SV4") (pin "2") (pinfunction "2_2") (pintype "passive"))
      (node (ref "SV4") (pin "4") (pinfunction "4_4") (pintype "passive"))
      (node (ref "SV4") (pin "6") (pinfunction "6_6") (pintype "passive"))
      (node (ref "SV4") (pin "8") (pinfunction "8_8") (pintype "passive"))
    )
    (net (code "41") (name "Net-(SV5-Pad1)") (class "Default")
      (node (ref "SV5") (pin "1") (pinfunction "1_1") (pintype "passive"))
      (node (ref "SV5") (pin "3") (pinfunction "3_3") (pintype "passive"))
      (node (ref "SV5") (pin "5") (pinfunction "5_5") (pintype "passive"))
      (node (ref "SV5") (pin "7") (pinfunction "7_7") (pintype "passive"))
    )
    (net (code "42") (name "Net-(SV5-Pad2)") (class "Default")
      (node (ref "SV5") (pin "2") (pinfunction "2_2") (pintype "passive"))
      (node (ref "SV5") (pin "4") (pinfunction "4_4") (pintype "passive"))
      (node (ref "SV5") (pin "6") (pinfunction "6_6") (pintype "passive"))
      (node (ref "SV5") (pin "8") (pinfunction "8_8") (pintype "passive"))
    )
    (net (code "43") (name "Net-(SV6-Pad1)") (class "Default")
      (node (ref "SV6") (pin "1") (pinfunction "1_1") (pintype "passive"))
      (node (ref "SV6") (pin "3") (pinfunction "3_3") (pintype "passive"))
      (node (ref "SV6") (pin "5") (pinfunction "5_5") (pintype "passive"))
      (node (ref "SV6") (pin "7") (pinfunction "7_7") (pintype "passive"))
    )
    (net (code "44") (name "Net-(SV6-Pad2)") (class "Default")
      (node (ref "SV6") (pin "2") (pinfunction "2_2") (pintype "passive"))
      (node (ref "SV6") (pin "4") (pinfunction "4_4") (pintype "passive"))
      (node (ref "SV6") (pin "6") (pinfunction "6_6") (pintype "passive"))
      (node (ref "SV6") (pin "8") (pinfunction "8_8") (pintype "passive"))
    )
    (net (code "45") (name "Net-(SV7-Pad1)") (class "Default")
      (node (ref "SV7") (pin "1") (pinfunction "1_1") (pintype "passive"))
      (node (ref "SV7") (pin "3") (pinfunction "3_3") (pintype "passive"))
      (node (ref "SV7") (pin "5") (pinfunction "5_5") (pintype "passive"))
      (node (ref "SV7") (pin "7") (pinfunction "7_7") (pintype "passive"))
    )
    (net (code "46") (name "Net-(SV7-Pad2)") (class "Default")
      (node (ref "SV7") (pin "2") (pinfunction "2_2") (pintype "passive"))
      (node (ref "SV7") (pin "4") (pinfunction "4_4") (pintype "passive"))
      (node (ref "SV7") (pin "6") (pinfunction "6_6") (pintype "passive"))
      (node (ref "SV7") (pin "8") (pinfunction "8_8") (pintype "passive"))
    )
    (net (code "47") (name "Net-(SV8-Pad1)") (class "Default")
      (node (ref "SV8") (pin "1") (pinfunction "1_1") (pintype "passive"))
      (node (ref "SV8") (pin "3") (pinfunction "3_3") (pintype "passive"))
      (node (ref "SV8") (pin "5") (pinfunction "5_5") (pintype "passive"))
      (node (ref "SV8") (pin "7") (pinfunction "7_7") (pintype "passive"))
    )
    (net (code "48") (name "Net-(SV8-Pad2)") (class "Default")
      (node (ref "SV8") (pin "2") (pinfunction "2_2") (pintype "passive"))
      (node (ref "SV8") (pin "4") (pinfunction "4_4") (pintype "passive"))
      (node (ref "SV8") (pin "6") (pinfunction "6_6") (pintype "passive"))
      (node (ref "SV8") (pin "8") (pinfunction "8_8") (pintype "passive"))
    )
    (net (code "49") (name "Net-(SV9-Pad1)") (class "Default")
      (node (ref "SV9") (pin "1") (pinfunction "1_1") (pintype "passive"))
      (node (ref "SV9") (pin "3") (pinfunction "3_3") (pintype "passive"))
      (node (ref "SV9") (pin "5") (pinfunction "5_5") (pintype "passive"))
      (node (ref "SV9") (pin "7") (pinfunction "7_7") (pintype "passive"))
    )
    (net (code "50") (name "Net-(SV9-Pad2)") (class "Default")
      (node (ref "SV9") (pin "2") (pinfunction "2_2") (pintype "passive"))
      (node (ref "SV9") (pin "4") (pinfunction "4_4") (pintype "passive"))
      (node (ref "SV9") (pin "6") (pinfunction "6_6") (pintype "passive"))
      (node (ref "SV9") (pin "8") (pinfunction "8_8") (pintype "passive"))
    )
    (net (code "51") (name "Net-(SV10-Pad1)") (class "Default")
      (node (ref "SV10") (pin "1") (pinfunction "1_1") (pintype "passive"))
      (node (ref "SV10") (pin "3") (pinfunction "3_3") (pintype "passive"))
      (node (ref "SV10") (pin "5") (pinfunction "5_5") (pintype "passive"))
      (node (ref "SV10") (pin "7") (pinfunction "7_7") (pintype "passive"))
    )
    (net (code "52") (name "Net-(SV10-Pad2)") (class "Default")
      (node (ref "SV10") (pin "2") (pinfunction "2_2") (pintype "passive"))
      (node (ref "SV10") (pin "4") (pinfunction "4_4") (pintype "passive"))
      (node (ref "SV10") (pin "6") (pinfunction "6_6") (pintype "passive"))
      (node (ref "SV10") (pin "8") (pinfunction "8_8") (pintype "passive"))
    )
    (net (code "53") (name "Net-(SV11-Pad1)") (class "Default")
      (node (ref "SV11") (pin "1") (pinfunction "1_1") (pintype "passive"))
      (node (ref "SV11") (pin "3") (pinfunction "3_3") (pintype "passive"))
      (node (ref "SV11") (pin "5") (pinfunction "5_5") (pintype "passive"))
      (node (ref "SV11") (pin "7") (pinfunction "7_7") (pintype "passive"))
    )
    (net (code "54") (name "Net-(SV11-Pad2)") (class "Default")
      (node (ref "SV11") (pin "2") (pinfunction "2_2") (pintype "passive"))
      (node (ref "SV11") (pin "4") (pinfunction "4_4") (pintype "passive"))
      (node (ref "SV11") (pin "6") (pinfunction "6_6") (pintype "passive"))
      (node (ref "SV11") (pin "8") (pinfunction "8_8") (pintype "passive"))
    )
    (net (code "55") (name "Net-(SV12-Pad1)") (class "Default")
      (node (ref "SV12") (pin "1") (pinfunction "1_1") (pintype "passive"))
      (node (ref "SV12") (pin "3") (pinfunction "3_3") (pintype "passive"))
      (node (ref "SV12") (pin "5") (pinfunction "5_5") (pintype "passive"))
      (node (ref "SV12") (pin "7") (pinfunction "7_7") (pintype "passive"))
    )
    (net (code "56") (name "Net-(SV12-Pad2)") (class "Default")
      (node (ref "SV12") (pin "2") (pinfunction "2_2") (pintype "passive"))
      (node (ref "SV12") (pin "4") (pinfunction "4_4") (pintype "passive"))
      (node (ref "SV12") (pin "6") (pinfunction "6_6") (pintype "passive"))
      (node (ref "SV12") (pin "8") (pinfunction "8_8") (pintype "passive"))
    )
    (net (code "57") (name "Net-(SV13-Pad1)") (class "Default")
      (node (ref "SV13") (pin "1") (pinfunction "1_1") (pintype "passive"))
      (node (ref "SV13") (pin "3") (pinfunction "3_3") (pintype "passive"))
      (node (ref "SV13") (pin "5") (pinfunction "5_5") (pintype "passive"))
      (node (ref "SV13") (pin "7") (pinfunction "7_7") (pintype "passive"))
    )
    (net (code "58") (name "Net-(SV13-Pad2)") (class "Default")
      (node (ref "SV13") (pin "2") (pinfunction "2_2") (pintype "passive"))
      (node (ref "SV13") (pin "4") (pinfunction "4_4") (pintype "passive"))
      (node (ref "SV13") (pin "6") (pinfunction "6_6") (pintype "passive"))
      (node (ref "SV13") (pin "8") (pinfunction "8_8") (pintype "passive"))
    )
    (net (code "59") (name "Net-(SV14-Pad1)") (class "Default")
      (node (ref "SV14") (pin "1") (pinfunction "1_1") (pintype "passive"))
      (node (ref "SV14") (pin "3") (pinfunction "3_3") (pintype "passive"))
      (node (ref "SV14") (pin "5") (pinfunction "5_5") (pintype "passive"))
      (node (ref "SV14") (pin "7") (pinfunction "7_7") (pintype "passive"))
    )
    (net (code "60") (name "Net-(SV14-Pad2)") (class "Default")
      (node (ref "SV14") (pin "2") (pinfunction "2_2") (pintype "passive"))
      (node (ref "SV14") (pin "4") (pinfunction "4_4") (pintype "passive"))
      (node (ref "SV14") (pin "6") (pinfunction "6_6") (pintype "passive"))
      (node (ref "SV14") (pin "8") (pinfunction "8_8") (pintype "passive"))
    )
    (net (code "61") (name "Net-(SV15-Pad1)") (class "Default")
      (node (ref "SV15") (pin "1") (pinfunction "1_1") (pintype "passive"))
      (node (ref "SV15") (pin "3") (pinfunction "3_3") (pintype "passive"))
      (node (ref "SV15") (pin "5") (pinfunction "5_5") (pintype "passive"))
      (node (ref "SV15") (pin "7") (pinfunction "7_7") (pintype "passive"))
    )
    (net (code "62") (name "Net-(SV15-Pad2)") (class "Default")
      (node (ref "SV15") (pin "2") (pinfunction "2_2") (pintype "passive"))
      (node (ref "SV15") (pin "4") (pinfunction "4_4") (pintype "passive"))
      (node (ref "SV15") (pin "6") (pinfunction "6_6") (pintype "passive"))
      (node (ref "SV15") (pin "8") (pinfunction "8_8") (pintype "passive"))
    )
    (net (code "63") (name "Net-(SV16-Pad1)") (class "Default")
      (node (ref "SV16") (pin "1") (pinfunction "1_1") (pintype "passive"))
      (node (ref "SV16") (pin "3") (pinfunction "3_3") (pintype "passive"))
      (node (ref "SV16") (pin "5") (pinfunction "5_5") (pintype "passive"))
      (node (ref "SV16") (pin "7") (pinfunction "7_7") (pintype "passive"))
    )
    (net (code "64") (name "Net-(SV16-Pad2)") (class "Default")
      (node (ref "SV16") (pin "2") (pinfunction "2_2") (pintype "passive"))
      (node (ref "SV16") (pin "4") (pinfunction "4_4") (pintype "passive"))
      (node (ref "SV16") (pin "6") (pinfunction "6_6") (pintype "passive"))
      (node (ref "SV16") (pin "8") (pinfunction "8_8") (pintype "passive"))
    )
    (net (code "65") (name "Net-(SV17-Pad1)") (class "Default")
      (node (ref "SV17") (pin "1") (pinfunction "1_1") (pintype "passive"))
      (node (ref "SV17") (pin "3") (pinfunction "3_3") (pintype "passive"))
      (node (ref "SV17") (pin "5") (pinfunction "5_5") (pintype "passive"))
      (node (ref "SV17") (pin "7") (pinfunction "7_7") (pintype "passive"))
    )
    (net (code "66") (name "Net-(SV17-Pad2)") (class "Default")
      (node (ref "SV17") (pin "2") (pinfunction "2_2") (pintype "passive"))
      (node (ref "SV17") (pin "4") (pinfunction "4_4") (pintype "passive"))
      (node (ref "SV17") (pin "6") (pinfunction "6_6") (pintype "passive"))
      (node (ref "SV17") (pin "8") (pinfunction "8_8") (pintype "passive"))
    )
    (net (code "67") (name "Net-(SV18-Pad1)") (class "Default")
      (node (ref "SV18") (pin "1") (pinfunction "1_1") (pintype "passive"))
      (node (ref "SV18") (pin "3") (pinfunction "3_3") (pintype "passive"))
      (node (ref "SV18") (pin "5") (pinfunction "5_5") (pintype "passive"))
      (node (ref "SV18") (pin "7") (pinfunction "7_7") (pintype "passive"))
    )
    (net (code "68") (name "Net-(SV18-Pad2)") (class "Default")
      (node (ref "SV18") (pin "2") (pinfunction "2_2") (pintype "passive"))
      (node (ref "SV18") (pin "4") (pinfunction "4_4") (pintype "passive"))
      (node (ref "SV18") (pin "6") (pinfunction "6_6") (pintype "passive"))
      (node (ref "SV18") (pin "8") (pinfunction "8_8") (pintype "passive"))
    )
    (net (code "69") (name "Net-(SV19-Pad1)") (class "Default")
      (node (ref "SV19") (pin "1") (pinfunction "1_1") (pintype "passive"))
      (node (ref "SV19") (pin "3") (pinfunction "3_3") (pintype "passive"))
      (node (ref "SV19") (pin "5") (pinfunction "5_5") (pintype "passive"))
      (node (ref "SV19") (pin "7") (pinfunction "7_7") (pintype "passive"))
    )
    (net (code "70") (name "Net-(SV19-Pad2)") (class "Default")
      (node (ref "SV19") (pin "2") (pinfunction "2_2") (pintype "passive"))
      (node (ref "SV19") (pin "4") (pinfunction "4_4") (pintype "passive"))
      (node (ref "SV19") (pin "6") (pinfunction "6_6") (pintype "passive"))
      (node (ref "SV19") (pin "8") (pinfunction "8_8") (pintype "passive"))
    )
    (net (code "71") (name "Net-(SV20-Pad1)") (class "Default")
      (node (ref "SV20") (pin "1") (pinfunction "1_1") (pintype "passive"))
      (node (ref "SV20") (pin "3") (pinfunction "3_3") (pintype "passive"))
      (node (ref "SV20") (pin "5") (pinfunction "5_5") (pintype "passive"))
      (node (ref "SV20") (pin "7") (pinfunction "7_7") (pintype "passive"))
    )
    (net (code "72") (name "Net-(SV20-Pad2)") (class "Default")
      (node (ref "SV20") (pin "2") (pinfunction "2_2") (pintype "passive"))
      (node (ref "SV20") (pin "4") (pinfunction "4_4") (pintype "passive"))
      (node (ref "SV20") (pin "6") (pinfunction "6_6") (pintype "passive"))
      (node (ref "SV20") (pin "8") (pinfunction "8_8") (pintype "passive"))
    )
    (net (code "73") (name "Net-(SV21-Pad1)") (class "Default")
      (node (ref "SV21") (pin "1") (pinfunction "1_1") (pintype "passive"))
      (node (ref "SV21") (pin "3") (pinfunction "3_3") (pintype "passive"))
      (node (ref "SV21") (pin "5") (pinfunction "5_5") (pintype "passive"))
      (node (ref "SV21") (pin "7") (pinfunction "7_7") (pintype "passive"))
    )
    (net (code "74") (name "Net-(SV21-Pad2)") (class "Default")
      (node (ref "SV21") (pin "2") (pinfunction "2_2") (pintype "passive"))
      (node (ref "SV21") (pin "4") (pinfunction "4_4") (pintype "passive"))
      (node (ref "SV21") (pin "6") (pinfunction "6_6") (pintype "passive"))
      (node (ref "SV21") (pin "8") (pinfunction "8_8") (pintype "passive"))
    )
    (net (code "75") (name "Net-(SV22-Pad1)") (class "Default")
      (node (ref "SV22") (pin "1") (pinfunction "1_1") (pintype "passive"))
      (node (ref "SV22") (pin "3") (pinfunction "3_3") (pintype "passive"))
      (node (ref "SV22") (pin "5") (pinfunction "5_5") (pintype "passive"))
      (node (ref "SV22") (pin "7") (pinfunction "7_7") (pintype "passive"))
    )
    (net (code "76") (name "Net-(SV22-Pad2)") (class "Default")
      (node (ref "SV22") (pin "2") (pinfunction "2_2") (pintype "passive"))
      (node (ref "SV22") (pin "4") (pinfunction "4_4") (pintype "passive"))
      (node (ref "SV22") (pin "6") (pinfunction "6_6") (pintype "passive"))
      (node (ref "SV22") (pin "8") (pinfunction "8_8") (pintype "passive"))
    )
    (net (code "77") (name "Net-(SV23-Pad1)") (class "Default")
      (node (ref "SV23") (pin "1") (pinfunction "1_1") (pintype "passive"))
      (node (ref "SV23") (pin "3") (pinfunction "3_3") (pintype "passive"))
      (node (ref "SV23") (pin "5") (pinfunction "5_5") (pintype "passive"))
      (node (ref "SV23") (pin "7") (pinfunction "7_7") (pintype "passive"))
    )
    (net (code "78") (name "Net-(SV23-Pad2)") (class "Default")
      (node (ref "SV23") (pin "2") (pinfunction "2_2") (pintype "passive"))
      (node (ref "SV23") (pin "4") (pinfunction "4_4") (pintype "passive"))
      (node (ref "SV23") (pin "6") (pinfunction "6_6") (pintype "passive"))
      (node (ref "SV23") (pin "8") (pinfunction "8_8") (pintype "passive"))
    )
    (net (code "79") (name "Net-(SV24-Pad1)") (class "Default")
      (node (ref "SV24") (pin "1") (pinfunction "1_1") (pintype "passive"))
      (node (ref "SV24") (pin "3") (pinfunction "3_3") (pintype "passive"))
      (node (ref "SV24") (pin "5") (pinfunction "5_5") (pintype "passive"))
      (node (ref "SV24") (pin "7") (pinfunction "7_7") (pintype "passive"))
    )
    (net (code "80") (name "Net-(SV24-Pad2)") (class "Default")
      (node (ref "SV24") (pin "2") (pinfunction "2_2") (pintype "passive"))
      (node (ref "SV24") (pin "4") (pinfunction "4_4") (pintype "passive"))
      (node (ref "SV24") (pin "6") (pinfunction "6_6") (pintype "passive"))
      (node (ref "SV24") (pin "8") (pinfunction "8_8") (pintype "passive"))
    )
    (net (code "81") (name "Net-(SV25-Pad1)") (class "Default")
      (node (ref "SV25") (pin "1") (pinfunction "1_1") (pintype "passive"))
      (node (ref "SV25") (pin "3") (pinfunction "3_3") (pintype "passive"))
      (node (ref "SV25") (pin "5") (pinfunction "5_5") (pintype "passive"))
      (node (ref "SV25") (pin "7") (pinfunction "7_7") (pintype "passive"))
    )
    (net (code "82") (name "Net-(SV25-Pad2)") (class "Default")
      (node (ref "SV25") (pin "2") (pinfunction "2_2") (pintype "passive"))
      (node (ref "SV25") (pin "4") (pinfunction "4_4") (pintype "passive"))
      (node (ref "SV25") (pin "6") (pinfunction "6_6") (pintype "passive"))
      (node (ref "SV25") (pin "8") (pinfunction "8_8") (pintype "passive"))
    )
    (net (code "83") (name "Net-(SV26-Pad1)") (class "Default")
      (node (ref "SV26") (pin "1") (pinfunction "1_1") (pintype "passive"))
      (node (ref "SV26") (pin "3") (pinfunction "3_3") (pintype "passive"))
      (node (ref "SV26") (pin "5") (pinfunction "5_5") (pintype "passive"))
      (node (ref "SV26") (pin "7") (pinfunction "7_7") (pintype "passive"))
    )
    (net (code "84") (name "Net-(SV26-Pad2)") (class "Default")
      (node (ref "SV26") (pin "2") (pinfunction "2_2") (pintype "passive"))
      (node (ref "SV26") (pin "4") (pinfunction "4_4") (pintype "passive"))
      (node (ref "SV26") (pin "6") (pinfunction "6_6") (pintype "passive"))
      (node (ref "SV26") (pin "8") (pinfunction "8_8") (pintype "passive"))
    )
    (net (code "85") (name "Net-(SV27-Pad1)") (class "Default")
      (node (ref "SV27") (pin "1") (pinfunction "1_1") (pintype "passive"))
      (node (ref "SV27") (pin "3") (pinfunction "3_3") (pintype "passive"))
      (node (ref "SV27") (pin "5") (pinfunction "5_5") (pintype "passive"))
      (node (ref "SV27") (pin "7") (pinfunction "7_7") (pintype "passive"))
    )
    (net (code "86") (name "Net-(SV27-Pad2)") (class "Default")
      (node (ref "SV27") (pin "2") (pinfunction "2_2") (pintype "passive"))
      (node (ref "SV27") (pin "4") (pinfunction "4_4") (pintype "passive"))
      (node (ref "SV27") (pin "6") (pinfunction "6_6") (pintype "passive"))
      (node (ref "SV27") (pin "8") (pinfunction "8_8") (pintype "passive"))
    )
    (net (code "87") (name "Net-(SV28-Pad1)") (class "Default")
      (node (ref "SV28") (pin "1") (pinfunction "1_1") (pintype "passive"))
      (node (ref "SV28") (pin "3") (pinfunction "3_3") (pintype "passive"))
      (node (ref "SV28") (pin "5") (pinfunction "5_5") (pintype "passive"))
      (node (ref "SV28") (pin "7") (pinfunction "7_7") (pintype "passive"))
    )
    (net (code "88") (name "Net-(SV28-Pad2)") (class "Default")
      (node (ref "SV28") (pin "2") (pinfunction "2_2") (pintype "passive"))
      (node (ref "SV28") (pin "4") (pinfunction "4_4") (pintype "passive"))
      (node (ref "SV28") (pin "6") (pinfunction "6_6") (pintype "passive"))
      (node (ref "SV28") (pin "8") (pinfunction "8_8") (pintype "passive"))
    )
    (net (code "89") (name "Net-(SV29-Pad1)") (class "Default")
      (node (ref "SV29") (pin "1") (pinfunction "1_1") (pintype "passive"))
      (node (ref "SV29") (pin "3") (pinfunction "3_3") (pintype "passive"))
      (node (ref "SV29") (pin "5") (pinfunction "5_5") (pintype "passive"))
      (node (ref "SV29") (pin "7") (pinfunction "7_7") (pintype "passive"))
    )
    (net (code "90") (name "Net-(SV29-Pad2)") (class "Default")
      (node (ref "SV29") (pin "2") (pinfunction "2_2") (pintype "passive"))
      (node (ref "SV29") (pin "4") (pinfunction "4_4") (pintype "passive"))
      (node (ref "SV29") (pin "6") (pinfunction "6_6") (pintype "passive"))
      (node (ref "SV29") (pin "8") (pinfunction "8_8") (pintype "passive"))
    )
    (net (code "91") (name "Net-(SV30-Pad1)") (class "Default")
      (node (ref "SV30") (pin "1") (pinfunction "1_1") (pintype "passive"))
      (node (ref "SV30") (pin "3") (pinfunction "3_3") (pintype "passive"))
      (node (ref "SV30") (pin "5") (pinfunction "5_5") (pintype "passive"))
      (node (ref "SV30") (pin "7") (pinfunction "7_7") (pintype "passive"))
    )
    (net (code "92") (name "Net-(SV30-Pad2)") (class "Default")
      (node (ref "SV30") (pin "2") (pinfunction "2_2") (pintype "passive"))
      (node (ref "SV30") (pin "4") (pinfunction "4_4") (pintype "passive"))
      (node (ref "SV30") (pin "6") (pinfunction "6_6") (pintype "passive"))
      (node (ref "SV30") (pin "8") (pinfunction "8_8") (pintype "passive"))
    )
    (net (code "93") (name "Net-(SV31-Pad1)") (class "Default")
      (node (ref "SV31") (pin "1") (pinfunction "1_1") (pintype "passive"))
      (node (ref "SV31") (pin "3") (pinfunction "3_3") (pintype "passive"))
      (node (ref "SV31") (pin "5") (pinfunction "5_5") (pintype "passive"))
      (node (ref "SV31") (pin "7") (pinfunction "7_7") (pintype "passive"))
    )
    (net (code "94") (name "Net-(SV31-Pad2)") (class "Default")
      (node (ref "SV31") (pin "2") (pinfunction "2_2") (pintype "passive"))
      (node (ref "SV31") (pin "4") (pinfunction "4_4") (pintype "passive"))
      (node (ref "SV31") (pin "6") (pinfunction "6_6") (pintype "passive"))
      (node (ref "SV31") (pin "8") (pinfunction "8_8") (pintype "passive"))
    )
    (net (code "95") (name "Net-(SV32-Pad1)") (class "Default")
      (node (ref "SV32") (pin "1") (pinfunction "1_1") (pintype "passive"))
      (node (ref "SV32") (pin "3") (pinfunction "3_3") (pintype "passive"))
      (node (ref "SV32") (pin "5") (pinfunction "5_5") (pintype "passive"))
      (node (ref "SV32") (pin "7") (pinfunction "7_7") (pintype "passive"))
    )
    (net (code "96") (name "Net-(SV32-Pad2)") (class "Default")
      (node (ref "SV32") (pin "2") (pinfunction "2_2") (pintype "passive"))
      (node (ref "SV32") (pin "4") (pinfunction "4_4") (pintype "passive"))
      (node (ref "SV32") (pin "6") (pinfunction "6_6") (pintype "passive"))
      (node (ref "SV32") (pin "8") (pinfunction "8_8") (pintype "passive"))
    )
    (net (code "97") (name "Net-(SV33-Pad1)") (class "Default")
      (node (ref "SV33") (pin "1") (pinfunction "1_1") (pintype "passive"))
      (node (ref "SV33") (pin "3") (pinfunction "3_3") (pintype "passive"))
      (node (ref "SV33") (pin "5") (pinfunction "5_5") (pintype "passive"))
      (node (ref "SV33") (pin "7") (pinfunction "7_7") (pintype "passive"))
    )
    (net (code "98") (name "Net-(SV33-Pad2)") (class "Default")
      (node (ref "SV33") (pin "2") (pinfunction "2_2") (pintype "passive"))
      (node (ref "SV33") (pin "4") (pinfunction "4_4") (pintype "passive"))
      (node (ref "SV33") (pin "6") (pinfunction "6_6") (pintype "passive"))
      (node (ref "SV33") (pin "8") (pinfunction "8_8") (pintype "passive"))
    )
    (net (code "99") (name "Net-(SV34-Pad1)") (class "Default")
      (node (ref "SV34") (pin "1") (pinfunction "1_1") (pintype "passive"))
      (node (ref "SV34") (pin "3") (pinfunction "3_3") (pintype "passive"))
      (node (ref "SV34") (pin "5") (pinfunction "5_5") (pintype "passive"))
      (node (ref "SV34") (pin "7") (pinfunction "7_7") (pintype "passive"))
    )
    (net (code "100") (name "Net-(SV34-Pad2)") (class "Default")
      (node (ref "SV34") (pin "2") (pinfunction "2_2") (pintype "passive"))
      (node (ref "SV34") (pin "4") (pinfunction "4_4") (pintype "passive"))
      (node (ref "SV34") (pin "6") (pinfunction "6_6") (pintype "passive"))
      (node (ref "SV34") (pin "8") (pinfunction "8_8") (pintype "passive"))
    )
    (net (code "101") (name "Net-(SV35-Pad1)") (class "Default")
      (node (ref "SV35") (pin "1") (pinfunction "1_1") (pintype "passive"))
      (node (ref "SV35") (pin "3") (pinfunction "3_3") (pintype "passive"))
      (node (ref "SV35") (pin "5") (pinfunction "5_5") (pintype "passive"))
      (node (ref "SV35") (pin "7") (pinfunction "7_7") (pintype "passive"))
    )
    (net (code "102") (name "Net-(SV35-Pad2)") (class "Default")
      (node (ref "SV35") (pin "2") (pinfunction "2_2") (pintype "passive"))
      (node (ref "SV35") (pin "4") (pinfunction "4_4") (pintype "passive"))
      (node (ref "SV35") (pin "6") (pinfunction "6_6") (pintype "passive"))
      (node (ref "SV35") (pin "8") (pinfunction "8_8") (pintype "passive"))
    )
    (net (code "103") (name "Net-(SV36-Pad1)") (class "Default")
      (node (ref "SV36") (pin "1") (pinfunction "1_1") (pintype "passive"))
      (node (ref "SV36") (pin "3") (pinfunction "3_3") (pintype "passive"))
      (node (ref "SV36") (pin "5") (pinfunction "5_5") (pintype "passive"))
      (node (ref "SV36") (pin "7") (pinfunction "7_7") (pintype "passive"))
    )
    (net (code "104") (name "Net-(SV36-Pad2)") (class "Default")
      (node (ref "SV36") (pin "2") (pinfunction "2_2") (pintype "passive"))
      (node (ref "SV36") (pin "4") (pinfunction "4_4") (pintype "passive"))
      (node (ref "SV36") (pin "6") (pinfunction "6_6") (pintype "passive"))
      (node (ref "SV36") (pin "8") (pinfunction "8_8") (pintype "passive"))
    )
    (net (code "105") (name "Net-(SV37-Pad1)") (class "Default")
      (node (ref "SV37") (pin "1") (pinfunction "1_1") (pintype "passive"))
      (node (ref "SV37") (pin "3") (pinfunction "3_3") (pintype "passive"))
      (node (ref "SV37") (pin "5") (pinfunction "5_5") (pintype "passive"))
      (node (ref "SV37") (pin "7") (pinfunction "7_7") (pintype "passive"))
    )
    (net (code "106") (name "Net-(SV38-Pad2)") (class "Default")
      (node (ref "SV38") (pin "2") (pinfunction "2_2") (pintype "passive"))
      (node (ref "SV38") (pin "4") (pinfunction "4_4") (pintype "passive"))
      (node (ref "SV38") (pin "6") (pinfunction "6_6") (pintype "passive"))
      (node (ref "SV38") (pin "8") (pinfunction "8_8") (pintype "passive"))
    )
    (net (code "107") (name "Net-(SV39-Pad1)") (class "Default")
      (node (ref "SV39") (pin "1") (pinfunction "1_1") (pintype "passive"))
      (node (ref "SV39") (pin "3") (pinfunction "3_3") (pintype "passive"))
      (node (ref "SV39") (pin "5") (pinfunction "5_5") (pintype "passive"))
      (node (ref "SV39") (pin "7") (pinfunction "7_7") (pintype "passive"))
    )
    (net (code "108") (name "Net-(SV39-Pad2)") (class "Default")
      (node (ref "SV39") (pin "2") (pinfunction "2_2") (pintype "passive"))
      (node (ref "SV39") (pin "4") (pinfunction "4_4") (pintype "passive"))
      (node (ref "SV39") (pin "6") (pinfunction "6_6") (pintype "passive"))
      (node (ref "SV39") (pin "8") (pinfunction "8_8") (pintype "passive"))
    )
    (net (code "109") (name "Net-(SV40-Pad1)") (class "Default")
      (node (ref "SV40") (pin "1") (pinfunction "1_1") (pintype "passive"))
      (node (ref "SV40") (pin "3") (pinfunction "3_3") (pintype "passive"))
      (node (ref "SV40") (pin "5") (pinfunction "5_5") (pintype "passive"))
      (node (ref "SV40") (pin "7") (pinfunction "7_7") (pintype "passive"))
    )
    (net (code "110") (name "Net-(SV40-Pad2)") (class "Default")
      (node (ref "SV40") (pin "2") (pinfunction "2_2") (pintype "passive"))
      (node (ref "SV40") (pin "4") (pinfunction "4_4") (pintype "passive"))
      (node (ref "SV40") (pin "6") (pinfunction "6_6") (pintype "passive"))
      (node (ref "SV40") (pin "8") (pinfunction "8_8") (pintype "passive"))
    )
    (net (code "111") (name "Net-(SV41-Pad1)") (class "Default")
      (node (ref "SV41") (pin "1") (pinfunction "1_1") (pintype "passive"))
      (node (ref "SV41") (pin "3") (pinfunction "3_3") (pintype "passive"))
      (node (ref "SV41") (pin "5") (pinfunction "5_5") (pintype "passive"))
      (node (ref "SV41") (pin "7") (pinfunction "7_7") (pintype "passive"))
    )
    (net (code "112") (name "Net-(SV41-Pad2)") (class "Default")
      (node (ref "SV41") (pin "2") (pinfunction "2_2") (pintype "passive"))
      (node (ref "SV41") (pin "4") (pinfunction "4_4") (pintype "passive"))
      (node (ref "SV41") (pin "6") (pinfunction "6_6") (pintype "passive"))
      (node (ref "SV41") (pin "8") (pinfunction "8_8") (pintype "passive"))
    )
    (net (code "113") (name "Net-(SV42-Pad1)") (class "Default")
      (node (ref "SV42") (pin "1") (pinfunction "1_1") (pintype "passive"))
      (node (ref "SV42") (pin "3") (pinfunction "3_3") (pintype "passive"))
      (node (ref "SV42") (pin "5") (pinfunction "5_5") (pintype "passive"))
      (node (ref "SV42") (pin "7") (pinfunction "7_7") (pintype "passive"))
    )
    (net (code "114") (name "Net-(SV42-Pad2)") (class "Default")
      (node (ref "SV42") (pin "2") (pinfunction "2_2") (pintype "passive"))
      (node (ref "SV42") (pin "4") (pinfunction "4_4") (pintype "passive"))
      (node (ref "SV42") (pin "6") (pinfunction "6_6") (pintype "passive"))
      (node (ref "SV42") (pin "8") (pinfunction "8_8") (pintype "passive"))
    )
    (net (code "115") (name "Net-(SV43-Pad1)") (class "Default")
      (node (ref "SV43") (pin "1") (pinfunction "1_1") (pintype "passive"))
      (node (ref "SV43") (pin "3") (pinfunction "3_3") (pintype "passive"))
      (node (ref "SV43") (pin "5") (pinfunction "5_5") (pintype "passive"))
      (node (ref "SV43") (pin "7") (pinfunction "7_7") (pintype "passive"))
    )
    (net (code "116") (name "Net-(SV43-Pad2)") (class "Default")
      (node (ref "SV43") (pin "2") (pinfunction "2_2") (pintype "passive"))
      (node (ref "SV43") (pin "4") (pinfunction "4_4") (pintype "passive"))
      (node (ref "SV43") (pin "6") (pinfunction "6_6") (pintype "passive"))
      (node (ref "SV43") (pin "8") (pinfunction "8_8") (pintype "passive"))
    )
    (net (code "117") (name "Net-(SV44-Pad1)") (class "Default")
      (node (ref "SV44") (pin "1") (pinfunction "1_1") (pintype "passive"))
      (node (ref "SV44") (pin "3") (pinfunction "3_3") (pintype "passive"))
      (node (ref "SV44") (pin "5") (pinfunction "5_5") (pintype "passive"))
      (node (ref "SV44") (pin "7") (pinfunction "7_7") (pintype "passive"))
    )
    (net (code "118") (name "Net-(SV44-Pad2)") (class "Default")
      (node (ref "SV44") (pin "2") (pinfunction "2_2") (pintype "passive"))
      (node (ref "SV44") (pin "4") (pinfunction "4_4") (pintype "passive"))
      (node (ref "SV44") (pin "6") (pinfunction "6_6") (pintype "passive"))
      (node (ref "SV44") (pin "8") (pinfunction "8_8") (pintype "passive"))
    )
    (net (code "119") (name "Net-(SV45-Pad1)") (class "Default")
      (node (ref "SV45") (pin "1") (pinfunction "1_1") (pintype "passive"))
      (node (ref "SV45") (pin "3") (pinfunction "3_3") (pintype "passive"))
      (node (ref "SV45") (pin "5") (pinfunction "5_5") (pintype "passive"))
      (node (ref "SV45") (pin "7") (pinfunction "7_7") (pintype "passive"))
    )
    (net (code "120") (name "Net-(SV45-Pad2)") (class "Default")
      (node (ref "SV45") (pin "2") (pinfunction "2_2") (pintype "passive"))
      (node (ref "SV45") (pin "4") (pinfunction "4_4") (pintype "passive"))
      (node (ref "SV45") (pin "6") (pinfunction "6_6") (pintype "passive"))
      (node (ref "SV45") (pin "8") (pinfunction "8_8") (pintype "passive"))
    )
    (net (code "121") (name "Net-(SV46-Pad1)") (class "Default")
      (node (ref "SV46") (pin "1") (pinfunction "1_1") (pintype "passive"))
      (node (ref "SV46") (pin "3") (pinfunction "3_3") (pintype "passive"))
      (node (ref "SV46") (pin "5") (pinfunction "5_5") (pintype "passive"))
      (node (ref "SV46") (pin "7") (pinfunction "7_7") (pintype "passive"))
    )
    (net (code "122") (name "Net-(SV46-Pad2)") (class "Default")
      (node (ref "SV46") (pin "2") (pinfunction "2_2") (pintype "passive"))
      (node (ref "SV46") (pin "4") (pinfunction "4_4") (pintype "passive"))
      (node (ref "SV46") (pin "6") (pinfunction "6_6") (pintype "passive"))
      (node (ref "SV46") (pin "8") (pinfunction "8_8") (pintype "passive"))
    )
    (net (code "123") (name "Net-(SV47-Pad1)") (class "Default")
      (node (ref "SV47") (pin "1") (pinfunction "1_1") (pintype "passive"))
      (node (ref "SV47") (pin "3") (pinfunction "3_3") (pintype "passive"))
      (node (ref "SV47") (pin "5") (pinfunction "5_5") (pintype "passive"))
      (node (ref "SV47") (pin "7") (pinfunction "7_7") (pintype "passive"))
    )
    (net (code "124") (name "Net-(SV48-Pad2)") (class "Default")
      (node (ref "SV48") (pin "2") (pinfunction "2_2") (pintype "passive"))
      (node (ref "SV48") (pin "4") (pinfunction "4_4") (pintype "passive"))
      (node (ref "SV48") (pin "6") (pinfunction "6_6") (pintype "passive"))
      (node (ref "SV48") (pin "8") (pinfunction "8_8") (pintype "passive"))
    )
    (net (code "125") (name "Net-(SV49-Pad1)") (class "Default")
      (node (ref "SV49") (pin "1") (pinfunction "1_1") (pintype "passive"))
      (node (ref "SV49") (pin "2") (pinfunction "2_2") (pintype "passive"))
      (node (ref "SV49") (pin "3") (pinfunction "3_3") (pintype "passive"))
    )
    (net (code "126") (name "Net-(SV50-Pad1)") (class "Default")
      (node (ref "SV50") (pin "1") (pinfunction "1_1") (pintype "passive"))
      (node (ref "SV50") (pin "2") (pinfunction "2_2") (pintype "passive"))
      (node (ref "SV50") (pin "3") (pinfunction "3_3") (pintype "passive"))
    )
    (net (code "127") (name "Net-(SV51-Pad1)") (class "Default")
      (node (ref "SV51") (pin "1") (pinfunction "1_1") (pintype "passive"))
      (node (ref "SV51") (pin "2") (pinfunction "2_2") (pintype "passive"))
      (node (ref "SV51") (pin "3") (pinfunction "3_3") (pintype "passive"))
    )
    (net (code "128") (name "Net-(SV52-Pad1)") (class "Default")
      (node (ref "SV52") (pin "1") (pinfunction "1_1") (pintype "passive"))
      (node (ref "SV52") (pin "2") (pinfunction "2_2") (pintype "passive"))
      (node (ref "SV52") (pin "3") (pinfunction "3_3") (pintype "passive"))
    )
    (net (code "129") (name "Net-(SV54-Pad1)") (class "Default")
      (node (ref "SV54") (pin "1") (pinfunction "1_1") (pintype "passive"))
      (node (ref "SV54") (pin "2") (pinfunction "2_2") (pintype "passive"))
      (node (ref "SV54") (pin "3") (pinfunction "3_3") (pintype "passive"))
      (node (ref "SV54") (pin "4") (pinfunction "4_4") (pintype "passive"))
    )
    (net (code "130") (name "Net-(SV55-Pad1)") (class "Default")
      (node (ref "SV55") (pin "1") (pinfunction "1_1") (pintype "passive"))
      (node (ref "SV55") (pin "2") (pinfunction "2_2") (pintype "passive"))
      (node (ref "SV55") (pin "3") (pinfunction "3_3") (pintype "passive"))
      (node (ref "SV55") (pin "4") (pinfunction "4_4") (pintype "passive"))
    )
    (net (code "131") (name "Net-(SV57-Pad1)") (class "Default")
      (node (ref "SV57") (pin "1") (pinfunction "1_1") (pintype "passive"))
      (node (ref "SV57") (pin "2") (pinfunction "2_2") (pintype "passive"))
      (node (ref "SV57") (pin "3") (pinfunction "3_3") (pintype "passive"))
    )
    (net (code "132") (name "Net-(SV58-Pad1)") (class "Default")
      (node (ref "SV58") (pin "1") (pinfunction "1_1") (pintype "passive"))
      (node (ref "SV58") (pin "2") (pinfunction "2_2") (pintype "passive"))
      (node (ref "SV58") (pin "3") (pinfunction "3_3") (pintype "passive"))
    )
    (net (code "133") (name "Net-(SV60-Pad1)") (class "Default")
      (node (ref "SV60") (pin "1") (pinfunction "1_1") (pintype "passive"))
      (node (ref "SV60") (pin "2") (pinfunction "2_2") (pintype "passive"))
      (node (ref "SV60") (pin "3") (pinfunction "3_3") (pintype "passive"))
      (node (ref "SV60") (pin "4") (pinfunction "4_4") (pintype "passive"))
    )
    (net (code "134") (name "Net-(SV61-Pad1)") (class "Default")
      (node (ref "SV61") (pin "1") (pinfunction "1_1") (pintype "passive"))
      (node (ref "SV61") (pin "2") (pinfunction "2_2") (pintype "passive"))
      (node (ref "SV61") (pin "3") (pinfunction "3_3") (pintype "passive"))
      (node (ref "SV61") (pin "4") (pinfunction "4_4") (pintype "passive"))
    )
    (net (code "135") (name "Net-(SV62-Pad1)") (class "Default")
      (node (ref "SV62") (pin "1") (pinfunction "1_1") (pintype "passive"))
      (node (ref "SV62") (pin "2") (pinfunction "2_2") (pintype "passive"))
      (node (ref "SV62") (pin "3") (pinfunction "3_3") (pintype "passive"))
      (node (ref "SV62") (pin "4") (pinfunction "4_4") (pintype "passive"))
    )
    (net (code "136") (name "Net-(SV63-Pad1)") (class "Default")
      (node (ref "SV63") (pin "1") (pinfunction "1_1") (pintype "passive"))
      (node (ref "SV63") (pin "2") (pinfunction "2_2") (pintype "passive"))
      (node (ref "SV63") (pin "3") (pinfunction "3_3") (pintype "passive"))
      (node (ref "SV63") (pin "4") (pinfunction "4_4") (pintype "passive"))
    )
    (net (code "137") (name "Net-(SV64-Pad1)") (class "Default")
      (node (ref "SV64") (pin "1") (pinfunction "1_1") (pintype "passive"))
      (node (ref "SV64") (pin "2") (pinfunction "2_2") (pintype "passive"))
      (node (ref "SV64") (pin "3") (pinfunction "3_3") (pintype "passive"))
      (node (ref "SV64") (pin "4") (pinfunction "4_4") (pintype "passive"))
    )
    (net (code "138") (name "Net-(SV65-Pad1)") (class "Default")
      (node (ref "SV65") (pin "1") (pinfunction "1_1") (pintype "passive"))
      (node (ref "SV65") (pin "2") (pinfunction "2_2") (pintype "passive"))
      (node (ref "SV65") (pin "3") (pinfunction "3_3") (pintype "passive"))
      (node (ref "SV65") (pin "4") (pinfunction "4_4") (pintype "passive"))
    )
    (net (code "139") (name "Net-(T-P)") (class "Default")
      (node (ref "T") (pin "1") (pinfunction "P_1") (pintype "passive"))
      (node (ref "U$1") (pin "T2") (pinfunction "1_T2") (pintype "bidirectional"))
    )
    (net (code "140") (name "Net-(U$1Q-1)") (class "Default")
      (node (ref "U") (pin "1") (pinfunction "P_1") (pintype "passive"))
      (node (ref "U$1") (pin "U2") (pinfunction "1_U2") (pintype "bidirectional"))
    )
    (net (code "141") (name "Net-(U$1R-1)") (class "Default")
      (node (ref "U$1") (pin "V2") (pinfunction "1_V2") (pintype "bidirectional"))
      (node (ref "V") (pin "1") (pinfunction "P_1") (pintype "passive"))
    )
  )
)
